# LED_RGB.net
KiCad netlist of a schematic drawn in EAGLE
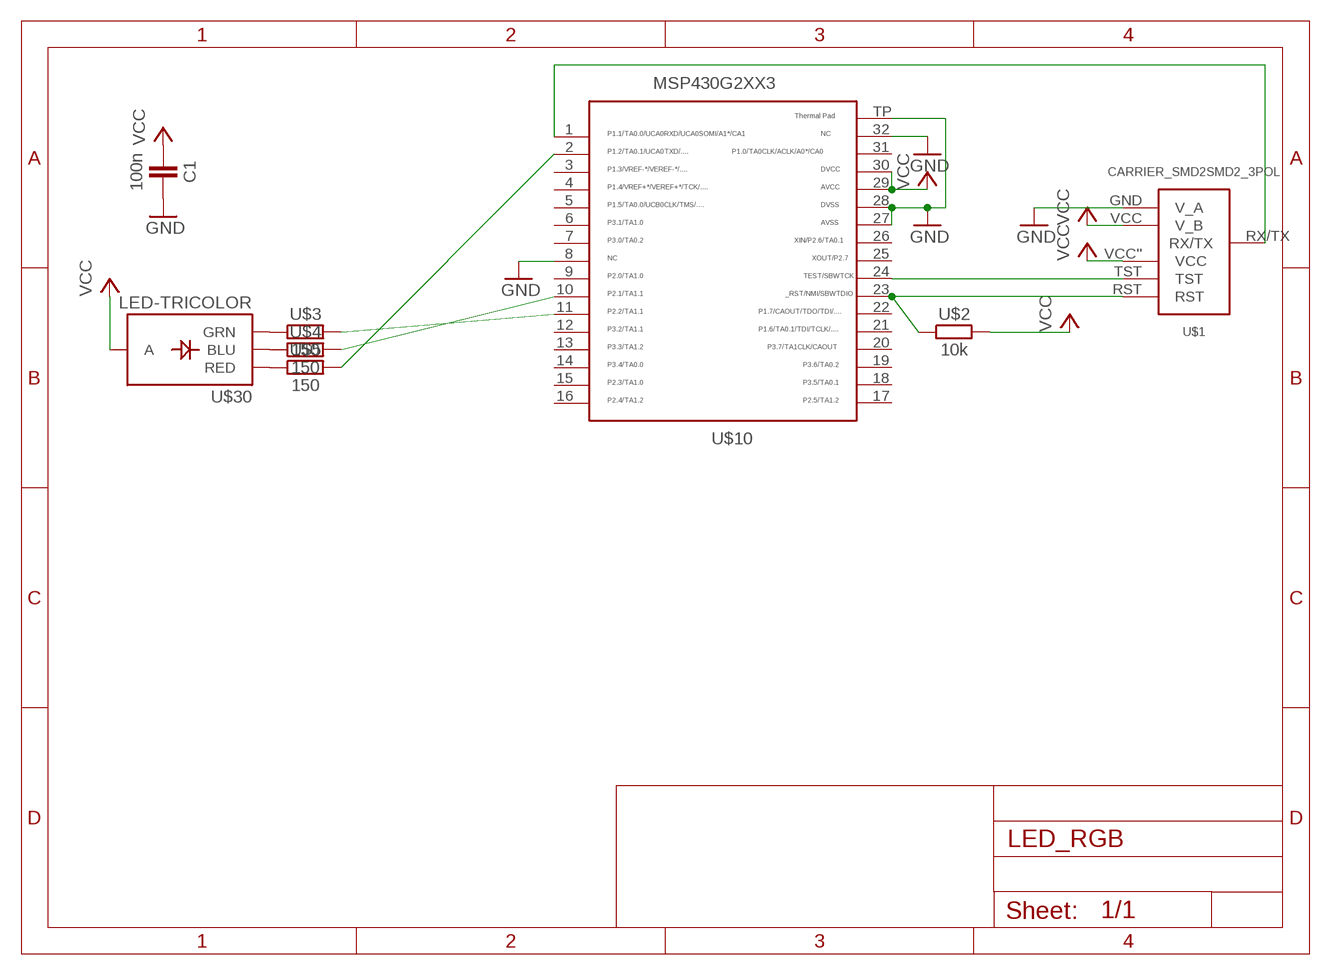
[diagram p0: schematic, sheet 1]

(export (version "E")
  (design (tool "Eeschema 10.0.6"))
  (components
    (comp (ref "C1")
      (value "100n")
      (footprint "eagle-import:603")
      (libsource (lib "eagle-import") (part "CAPACITOR"))
    )
    (comp (ref "U$1")
      (value "CARRIER_SMD2SMD2_3POL")
      (footprint "eagle-import:CARRIER_SMD2_3POL")
      (libsource (lib "eagle-import") (part "CARRIER_SMD2SMD2_3POL"))
    )
    (comp (ref "U$2")
      (value "10k")
      (footprint "eagle-import:603")
      (libsource (lib "eagle-import") (part "RESISTOR0603"))
    )
    (comp (ref "U$3")
      (value "150")
      (footprint "eagle-import:603")
      (libsource (lib "eagle-import") (part "RESISTOR0603"))
    )
    (comp (ref "U$4")
      (value "150")
      (footprint "eagle-import:603")
      (libsource (lib "eagle-import") (part "RESISTOR0603"))
    )
    (comp (ref "U$5")
      (value "150")
      (footprint "eagle-import:603")
      (libsource (lib "eagle-import") (part "RESISTOR0603"))
    )
    (comp (ref "U$10")
      (value "MSP430G2553")
      (footprint "eagle-import:QFN32")
      (libsource (lib "eagle-import") (part "MSP430G2553"))
    )
    (comp (ref "U$30")
      (value "LED-TRICOLOR")
      (footprint "eagle-import:LED-TRICOLOR-SMD")
      (libsource (lib "eagle-import") (part "LED-TRICOLOR"))
    )
  )
  (nets
    (net (code "1") (name "GND") (class "Default")
      (node (ref "C1") (pin "2") (pinfunction "2_2") (pintype "passive"))
      (node (ref "U$1") (pin "GND") (pinfunction "V_A_GND") (pintype "bidirectional"))
      (node (ref "U$10") (pin "27") (pinfunction "27_27") (pintype "bidirectional"))
      (node (ref "U$10") (pin "28") (pinfunction "28_28") (pintype "bidirectional"))
      (node (ref "U$10") (pin "32") (pinfunction "32_32") (pintype "bidirectional"))
      (node (ref "U$10") (pin "8") (pinfunction "8_8") (pintype "bidirectional"))
      (node (ref "U$10") (pin "TP") (pinfunction "TP_TP") (pintype "bidirectional"))
    )
    (net (code "2") (name "Net-(U$1-PadRST)") (class "Default")
      (node (ref "U$1") (pin "RST") (pinfunction "RST_RST") (pintype "bidirectional"))
      (node (ref "U$10") (pin "23") (pinfunction "23_23") (pintype "bidirectional"))
      (node (ref "U$2") (pin "1") (pinfunction "1_1") (pintype "passive"))
    )
    (net (code "3") (name "Net-(U$1-PadRX{slash}TX)") (class "Default")
      (node (ref "U$1") (pin "RX/TX") (pinfunction "RX/TX_RX/TX") (pintype "bidirectional"))
      (node (ref "U$10") (pin "1") (pinfunction "1_1") (pintype "bidirectional"))
    )
    (net (code "4") (name "Net-(U$1-PadTST)") (class "Default")
      (node (ref "U$1") (pin "TST") (pinfunction "TST_TST") (pintype "bidirectional"))
      (node (ref "U$10") (pin "24") (pinfunction "24_24") (pintype "bidirectional"))
    )
    (net (code "5") (name "Net-(U$10-Pad2)") (class "Default")
      (node (ref "U$10") (pin "2") (pinfunction "2_2") (pintype "bidirectional"))
      (node (ref "U$5") (pin "2") (pinfunction "2_2") (pintype "passive"))
    )
    (net (code "6") (name "Net-(U$10-Pad10)") (class "Default")
      (node (ref "U$10") (pin "10") (pinfunction "10_10") (pintype "bidirectional"))
      (node (ref "U$4") (pin "2") (pinfunction "2_2") (pintype "passive"))
    )
    (net (code "7") (name "Net-(U$10-Pad11)") (class "Default")
      (node (ref "U$10") (pin "11") (pinfunction "11_11") (pintype "bidirectional"))
      (node (ref "U$3") (pin "2") (pinfunction "2_2") (pintype "passive"))
    )
    (net (code "8") (name "Net-(U$30-BLU)") (class "Default")
      (node (ref "U$30") (pin "B") (pinfunction "BLU_B") (pintype "bidirectional"))
      (node (ref "U$4") (pin "1") (pinfunction "1_1") (pintype "passive"))
    )
    (net (code "9") (name "Net-(U$30-GRN)") (class "Default")
      (node (ref "U$3") (pin "1") (pinfunction "1_1") (pintype "passive"))
      (node (ref "U$30") (pin "G") (pinfunction "GRN_G") (pintype "bidirectional"))
    )
    (net (code "10") (name "Net-(U$30-RED)") (class "Default")
      (node (ref "U$30") (pin "R") (pinfunction "RED_R") (pintype "bidirectional"))
      (node (ref "U$5") (pin "1") (pinfunction "1_1") (pintype "passive"))
    )
    (net (code "11") (name "VCC") (class "Default")
      (node (ref "C1") (pin "1") (pinfunction "1_1") (pintype "passive"))
      (node (ref "U$1") (pin "VCC") (pinfunction "V_B_VCC") (pintype "bidirectional"))
      (node (ref "U$1") (pin "VCC''") (pinfunction "VCC_VCC''") (pintype "bidirectional"))
      (node (ref "U$10") (pin "29") (pinfunction "29_29") (pintype "bidirectional"))
      (node (ref "U$10") (pin "30") (pinfunction "30_30") (pintype "bidirectional"))
      (node (ref "U$2") (pin "2") (pinfunction "2_2") (pintype "passive"))
      (node (ref "U$30") (pin "A") (pinfunction "A_A") (pintype "bidirectional"))
    )
    (net (code "12") (name "unconnected-(U$10-Pad3)") (class "Default")
      (node (ref "U$10") (pin "3") (pinfunction "3_3") (pintype "bidirectional"))
    )
    (net (code "13") (name "unconnected-(U$10-Pad4)") (class "Default")
      (node (ref "U$10") (pin "4") (pinfunction "4_4") (pintype "bidirectional"))
    )
    (net (code "14") (name "unconnected-(U$10-Pad5)") (class "Default")
      (node (ref "U$10") (pin "5") (pinfunction "5_5") (pintype "bidirectional"))
    )
    (net (code "15") (name "unconnected-(U$10-Pad6)") (class "Default")
      (node (ref "U$10") (pin "6") (pinfunction "6_6") (pintype "bidirectional"))
    )
    (net (code "16") (name "unconnected-(U$10-Pad7)") (class "Default")
      (node (ref "U$10") (pin "7") (pinfunction "7_7") (pintype "bidirectional"))
    )
    (net (code "17") (name "unconnected-(U$10-Pad9)") (class "Default")
      (node (ref "U$10") (pin "9") (pinfunction "9_9") (pintype "bidirectional"))
    )
    (net (code "18") (name "unconnected-(U$10-Pad12)") (class "Default")
      (node (ref "U$10") (pin "12") (pinfunction "12_12") (pintype "bidirectional"))
    )
    (net (code "19") (name "unconnected-(U$10-Pad13)") (class "Default")
      (node (ref "U$10") (pin "13") (pinfunction "13_13") (pintype "bidirectional"))
    )
    (net (code "20") (name "unconnected-(U$10-Pad14)") (class "Default")
      (node (ref "U$10") (pin "14") (pinfunction "14_14") (pintype "bidirectional"))
    )
    (net (code "21") (name "unconnected-(U$10-Pad15)") (class "Default")
      (node (ref "U$10") (pin "15") (pinfunction "15_15") (pintype "bidirectional"))
    )
    (net (code "22") (name "unconnected-(U$10-Pad16)") (class "Default")
      (node (ref "U$10") (pin "16") (pinfunction "16_16") (pintype "bidirectional"))
    )
    (net (code "23") (name "unconnected-(U$10-Pad17)") (class "Default")
      (node (ref "U$10") (pin "17") (pinfunction "17_17") (pintype "bidirectional"))
    )
    (net (code "24") (name "unconnected-(U$10-Pad18)") (class "Default")
      (node (ref "U$10") (pin "18") (pinfunction "18_18") (pintype "bidirectional"))
    )
    (net (code "25") (name "unconnected-(U$10-Pad19)") (class "Default")
      (node (ref "U$10") (pin "19") (pinfunction "19_19") (pintype "bidirectional"))
    )
    (net (code "26") (name "unconnected-(U$10-Pad20)") (class "Default")
      (node (ref "U$10") (pin "20") (pinfunction "20_20") (pintype "bidirectional"))
    )
    (net (code "27") (name "unconnected-(U$10-Pad21)") (class "Default")
      (node (ref "U$10") (pin "21") (pinfunction "21_21") (pintype "bidirectional"))
    )
    (net (code "28") (name "unconnected-(U$10-Pad22)") (class "Default")
      (node (ref "U$10") (pin "22") (pinfunction "22_22") (pintype "bidirectional"))
    )
    (net (code "29") (name "unconnected-(U$10-Pad25)") (class "Default")
      (node (ref "U$10") (pin "25") (pinfunction "25_25") (pintype "bidirectional"))
    )
    (net (code "30") (name "unconnected-(U$10-Pad26)") (class "Default")
      (node (ref "U$10") (pin "26") (pinfunction "26_26") (pintype "bidirectional"))
    )
    (net (code "31") (name "unconnected-(U$10-Pad31)") (class "Default")
      (node (ref "U$10") (pin "31") (pinfunction "31_31") (pintype "bidirectional"))
    )
  )
)
